# main.net
KiCad netlist of a schematic drawn in Altium Designer
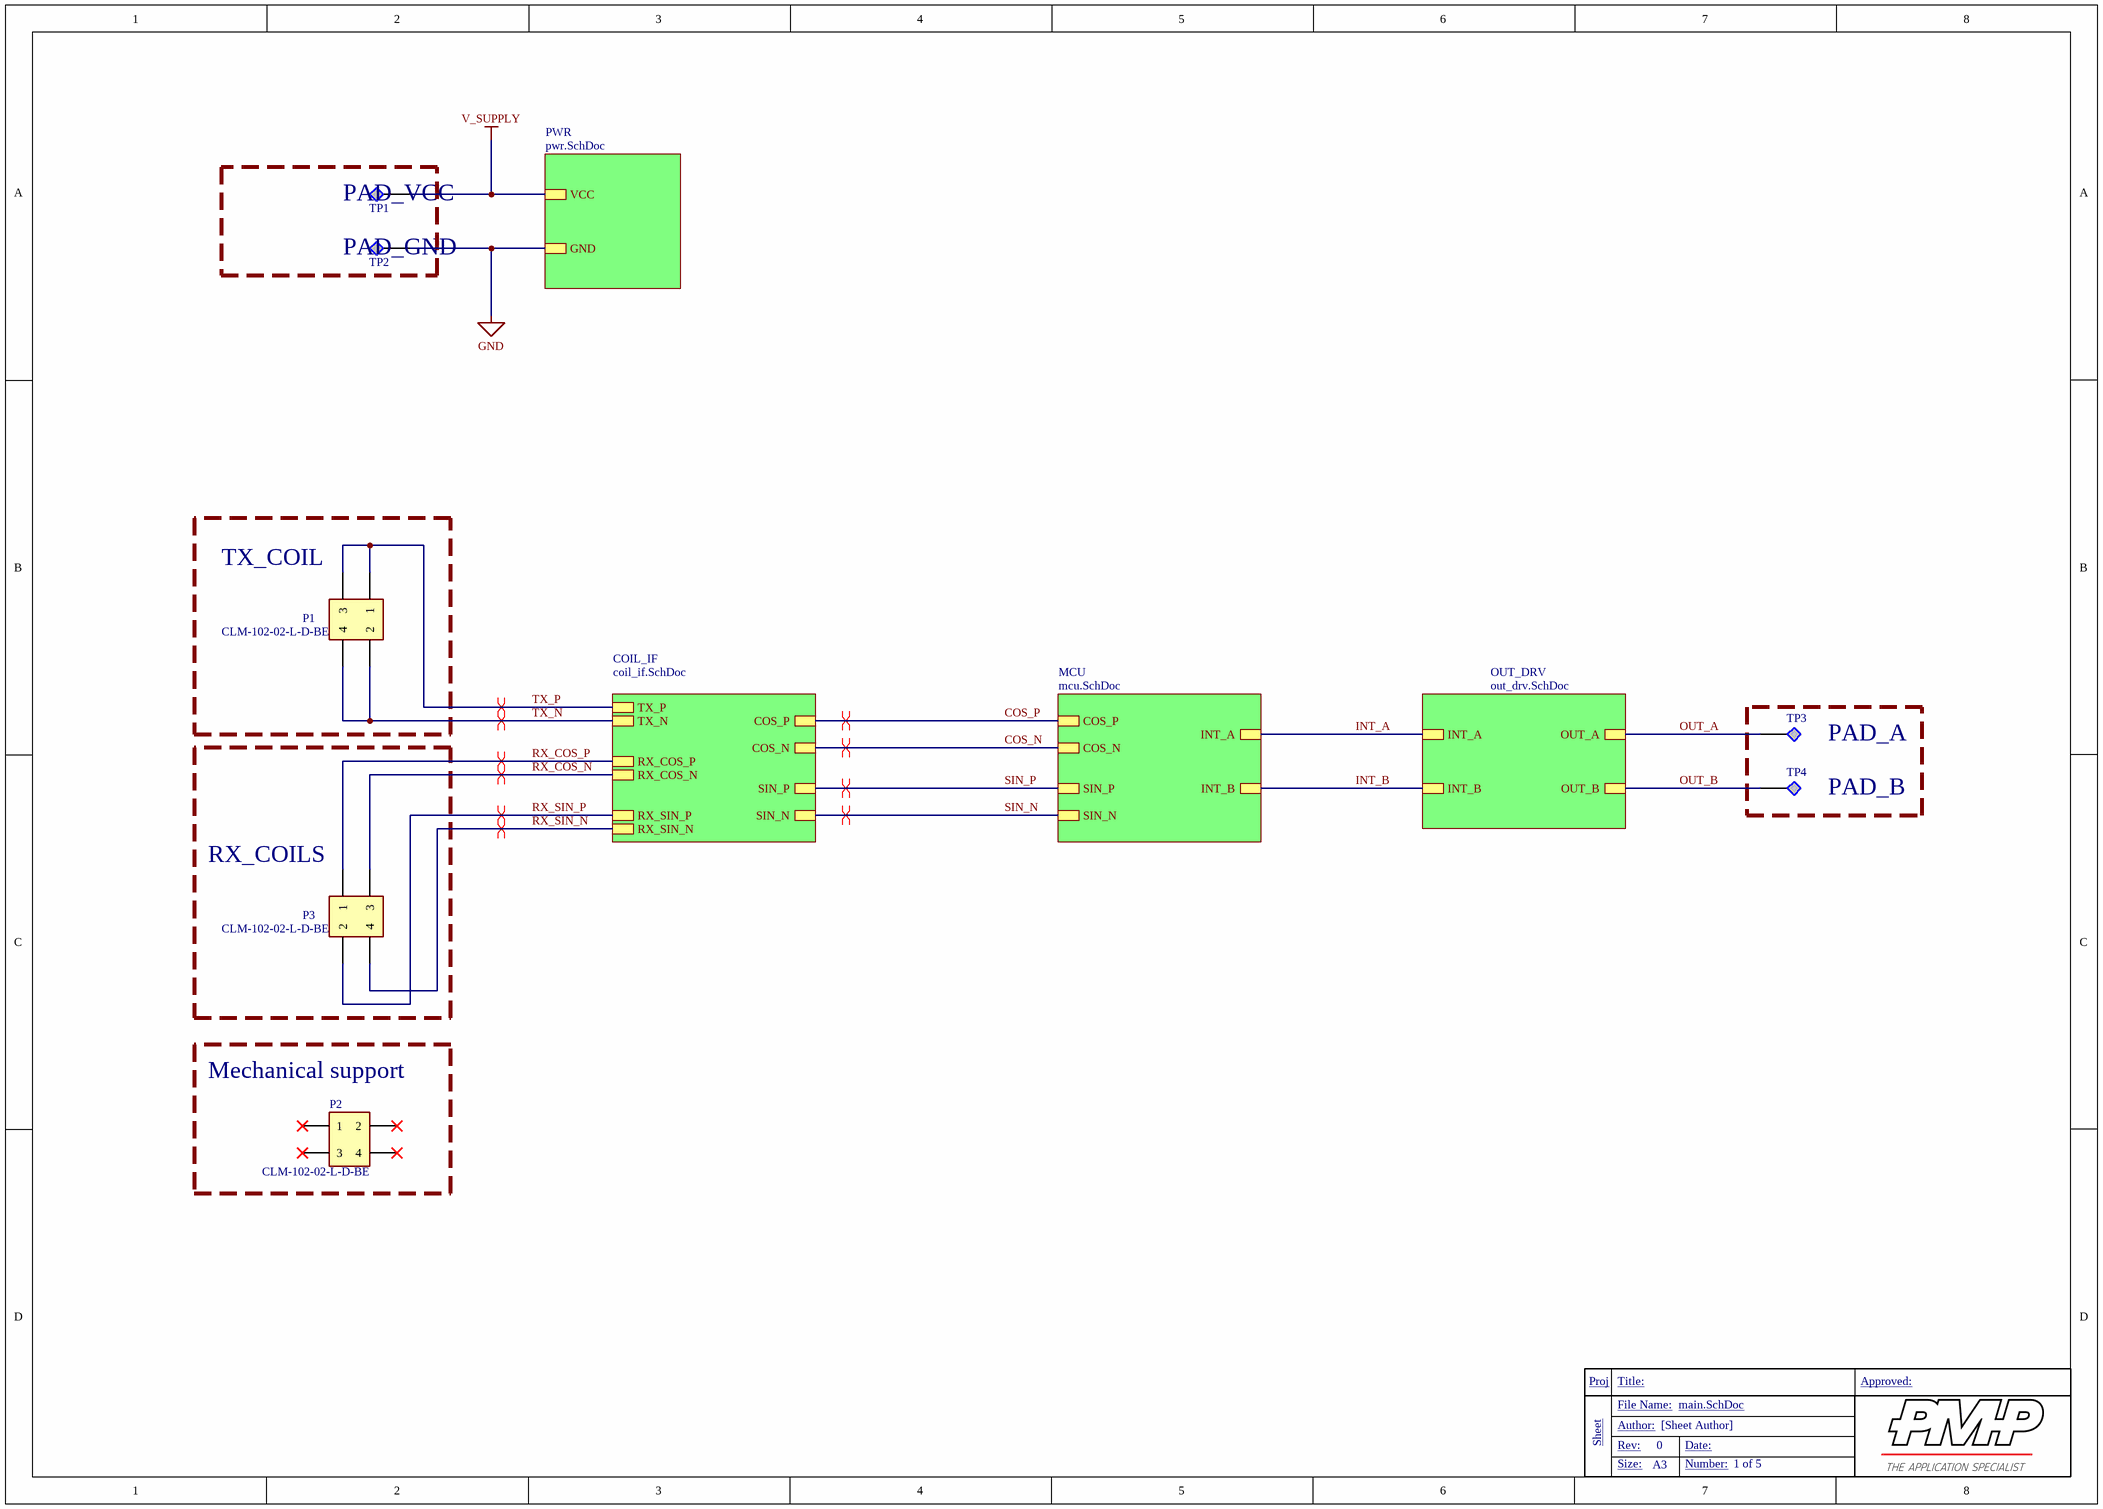
[diagram p0: main.SchDoc]

(export (version "E")
  (design (tool "Eeschema 10.0.6"))
  (components
    (comp (ref "P1")
      (value "CLM-102-02-L-D-BE")
      (footprint "SAMTEC_CLM-102-02-X-D-BE_SPECIAL")
      (description "Samtech Female header 2x2,pitch 1mm")
      (fields (field (name "MP") "TSW-108-07-G-S") (field (name "MF") "Samtec"))
      (libsource (lib "") (part "Conn_4_STRIP_2x2_2"))
    )
    (comp (ref "P2")
      (value "CLM-102-02-L-D-BE")
      (footprint "SAMTEC_CLM-102-02-X-D-BE_SPECIAL")
      (description "Samtech Female header 2x2,pitch 1mm")
      (fields (field (name "MP") "TSW-108-07-G-S") (field (name "MF") "Samtec"))
      (libsource (lib "") (part "Conn_4_STRIP_2x2_1"))
    )
    (comp (ref "P3")
      (value "CLM-102-02-L-D-BE")
      (footprint "SAMTEC_CLM-102-02-X-D-BE_SPECIAL")
      (description "Samtech Female header 2x2,pitch 1mm")
      (fields (field (name "MP") "TSW-108-07-G-S") (field (name "MF") "Samtec"))
      (libsource (lib "PMP_ConnectorsDB") (part "Conn_4_STRIP_2x2"))
    )
    (comp (ref "TP1")
      (value "Term Pole")
      (footprint "Terminale 508-0685_2mm")
      (description "Occhiello PTH, 1mm, Black, Plated")
      (libsource (lib "PMP_ConnectorsDB") (part "Occhiello"))
    )
    (comp (ref "TP2")
      (value "Term Pole")
      (footprint "Terminale 508-0685_2mm")
      (description "Occhiello PTH, 1mm, Black, Plated")
      (libsource (lib "PMP_ConnectorsDB") (part "Occhiello"))
    )
    (comp (ref "TP3")
      (value "Term Pole")
      (footprint "Terminale 508-0685_2mm")
      (description "Occhiello PTH, 1mm, Black, Plated")
      (libsource (lib "PMP_ConnectorsDB") (part "Occhiello"))
    )
    (comp (ref "TP4")
      (value "Term Pole")
      (footprint "Terminale 508-0685_2mm")
      (description "Occhiello PTH, 1mm, Black, Plated")
      (libsource (lib "PMP_ConnectorsDB") (part "Occhiello"))
    )
  )
  (nets
    (net (code "5") (name "/OUT_A") (class "Default")
      (node (ref "TP3") (pin "1") (pinfunction "1_1") (pintype "passive"))
    )
    (net (code "6") (name "/OUT_B") (class "Default")
      (node (ref "TP4") (pin "1") (pinfunction "1_1") (pintype "passive"))
    )
    (net (code "7") (name "/RX_COS_N") (class "Default")
      (node (ref "P3") (pin "03") (pinfunction "3_03") (pintype "passive"))
    )
    (net (code "8") (name "/RX_COS_P") (class "Default")
      (node (ref "P3") (pin "01") (pinfunction "1_01") (pintype "passive"))
    )
    (net (code "9") (name "/RX_SIN_N") (class "Default")
      (node (ref "P3") (pin "04") (pinfunction "4_04") (pintype "passive"))
    )
    (net (code "10") (name "/RX_SIN_P") (class "Default")
      (node (ref "P3") (pin "02") (pinfunction "2_02") (pintype "passive"))
    )
    (net (code "13") (name "/TX_N") (class "Default")
      (node (ref "P1") (pin "02") (pinfunction "2_02") (pintype "passive"))
      (node (ref "P1") (pin "04") (pinfunction "4_04") (pintype "passive"))
    )
    (net (code "14") (name "/TX_P") (class "Default")
      (node (ref "P1") (pin "01") (pinfunction "1_01") (pintype "passive"))
      (node (ref "P1") (pin "03") (pinfunction "3_03") (pintype "passive"))
    )
    (net (code "15") (name "GND") (class "Default")
      (node (ref "TP2") (pin "1") (pinfunction "1_1") (pintype "passive"))
    )
    (net (code "16") (name "V_SUPPLY") (class "Default")
      (node (ref "TP1") (pin "1") (pinfunction "1_1") (pintype "passive"))
    )
    (net (code "17") (name "unconnected-(P2-1-Pad01)") (class "Default")
      (node (ref "P2") (pin "01") (pinfunction "1_01") (pintype "passive+no_connect"))
    )
    (net (code "18") (name "unconnected-(P2-2-Pad02)") (class "Default")
      (node (ref "P2") (pin "02") (pinfunction "2_02") (pintype "passive+no_connect"))
    )
    (net (code "19") (name "unconnected-(P2-3-Pad03)") (class "Default")
      (node (ref "P2") (pin "03") (pinfunction "3_03") (pintype "passive+no_connect"))
    )
    (net (code "20") (name "unconnected-(P2-4-Pad04)") (class "Default")
      (node (ref "P2") (pin "04") (pinfunction "4_04") (pintype "passive+no_connect"))
    )
  )
)
